# filter_pcb.net
KiCad netlist of a schematic drawn in Altium Designer
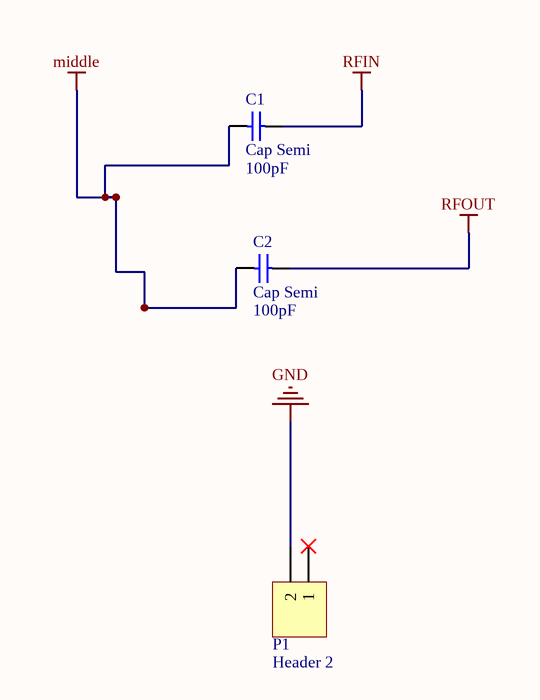
[diagram p0: filter pcb.SchDoc]

(export (version "E")
  (design (tool "Eeschema 10.0.6"))
  (components
    (comp (ref "C1")
      (value "Cap Semi")
      (footprint "C1206")
      (description "Capacitor (Semiconductor SIM Model)")
      (fields (field (name "ALTIUM_VALUE") "100pF") (field (name "PUBLISHER") "Altium Limited"))
      (libsource (lib "Miscellaneous Devices") (part "Cap Semi"))
    )
    (comp (ref "C2")
      (value "Cap Semi")
      (footprint "C1206")
      (description "Capacitor (Semiconductor SIM Model)")
      (fields (field (name "ALTIUM_VALUE") "100pF") (field (name "PUBLISHER") "Altium Limited"))
      (libsource (lib "Miscellaneous Devices") (part "Cap Semi"))
    )
    (comp (ref "P1")
      (value "Header 2")
      (footprint "HDR1X2")
      (description "Header, 2-Pin")
      (fields (field (name "PUBLISHER") "Altium Limited"))
      (libsource (lib "Miscellaneous Connectors") (part "Header 2"))
    )
  )
  (nets
    (net (code "1") (name "GND") (class "Default")
      (node (ref "P1") (pin "2") (pinfunction "2_2") (pintype "passive"))
    )
    (net (code "2") (name "RFIN") (class "Default")
      (node (ref "C1") (pin "2") (pinfunction "2_2") (pintype "passive"))
    )
    (net (code "3") (name "RFOUT") (class "Default")
      (node (ref "C2") (pin "2") (pinfunction "2_2") (pintype "passive"))
    )
    (net (code "4") (name "middle") (class "Default")
      (node (ref "C1") (pin "1") (pinfunction "1_1") (pintype "passive"))
      (node (ref "C2") (pin "1") (pinfunction "1_1") (pintype "passive"))
    )
    (net (code "5") (name "unconnected-(P1-Pad1)") (class "Default")
      (node (ref "P1") (pin "1") (pinfunction "1_1") (pintype "passive+no_connect"))
    )
  )
)
